# design.net
KiCad netlist of a schematic drawn in Altium Designer
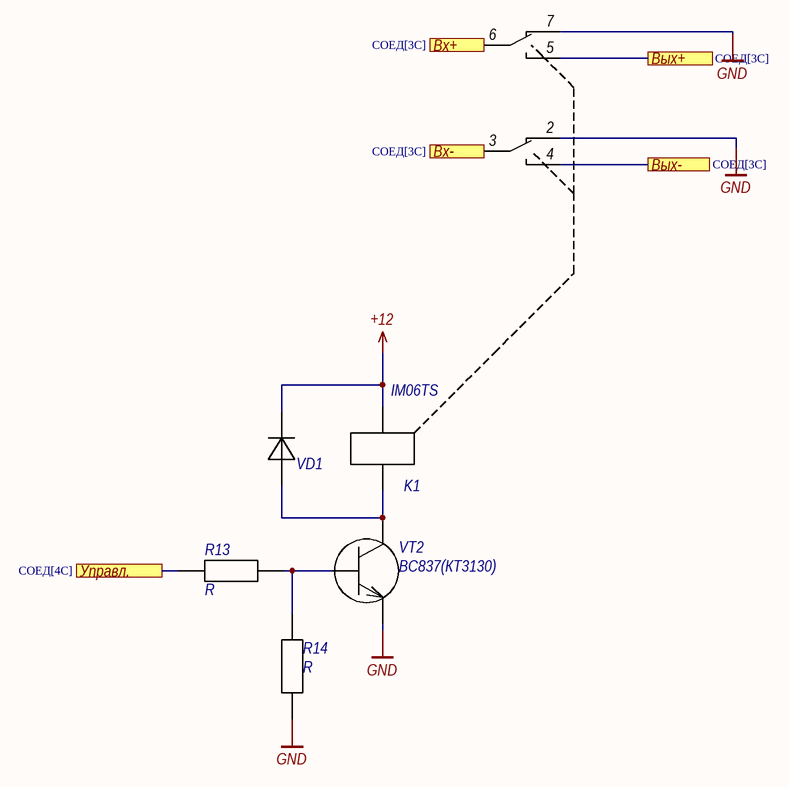
[diagram p0: РЕЛЕ.SchDoc]

(export (version "E")
  (design (tool "Eeschema 10.0.6"))
  (components
    (comp (ref "K1") (value "IM06TS") (footprint "IM06TS") (libsource (lib "UGO") (part "IM06TS")))
    (comp (ref "R13") (value "R") (footprint "R") (libsource (lib "") (part "R_1")))
    (comp (ref "R14") (value "R") (footprint "R") (libsource (lib "UGO") (part "R")))
    (comp (ref "VD1") (value "SS14") (footprint "SS14") (libsource (lib "UGO") (part "SS14")))
    (comp (ref "VT2")
      (value "BC837(КТ3130)")
      (footprint "BC847(IRLML6402)")
      (description "Транзистор")
      (libsource (lib "УГО мск") (part "BC837(КТ3130)"))
    )
  )
  (nets
    (net (code "1") (name "+12") (class "Default")
      (node (ref "K1") (pin "1") (pintype "passive"))
      (node (ref "VD1") (pin "1") (pintype "passive"))
    )
    (net (code "2") (name "/Вх+") (class "Default") (node (ref "K1") (pin "6") (pintype "passive")))
    (net (code "3") (name "/Вх-") (class "Default") (node (ref "K1") (pin "3") (pintype "passive")))
    (net (code "4") (name "/Вых+") (class "Default") (node (ref "K1") (pin "5") (pintype "passive")))
    (net (code "5") (name "/Вых-") (class "Default") (node (ref "K1") (pin "4") (pintype "passive")))
    (net (code "6") (name "/Управл.") (class "Default") (node (ref "R13") (pin "1") (pintype "passive")))
    (net (code "7") (name "GND") (class "Default")
      (node (ref "K1") (pin "2") (pintype "passive"))
      (node (ref "K1") (pin "7") (pintype "passive"))
      (node (ref "R14") (pin "1") (pintype "passive"))
      (node (ref "VT2") (pin "2") (pintype "passive"))
    )
    (net (code "8") (name "Net-(K1-Pad8)") (class "Default")
      (node (ref "K1") (pin "8") (pintype "passive"))
      (node (ref "VD1") (pin "2") (pintype "passive"))
      (node (ref "VT2") (pin "3") (pintype "passive"))
    )
    (net (code "9") (name "Net-(R13-Pad2)") (class "Default")
      (node (ref "R13") (pin "2") (pintype "passive"))
      (node (ref "R14") (pin "2") (pintype "passive"))
      (node (ref "VT2") (pin "1") (pintype "passive"))
    )
  )
)
